# Assignment-1.net
KiCad netlist of a schematic drawn in EAGLE
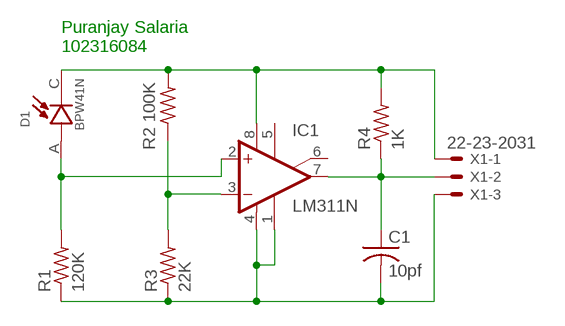
[diagram p0: schematic, sheet 1]

(export (version "E")
  (design (tool "Eeschema 10.0.6"))
  (components
    (comp (ref "C1")
      (value "10pf")
      (footprint "eagle-import:C025-050X050")
      (libsource (lib "eagle-import") (part "C-US025-050X050"))
    )
    (comp (ref "D1")
      (value "BPW41N")
      (footprint "eagle-import:DIO_BPW41N")
      (fields (field (name "MF") "Vishay Semiconductor Opto Division"))
      (libsource (lib "eagle-import") (part "BPW41N"))
    )
    (comp (ref "IC1")
      (value "LM311N")
      (footprint "eagle-import:DIL08")
      (libsource (lib "eagle-import") (part "LM311N"))
    )
    (comp (ref "R1")
      (value "120K")
      (footprint "eagle-import:0204_7")
      (libsource (lib "eagle-import") (part "R-US_0204/7"))
    )
    (comp (ref "R2")
      (value "R2 100K")
      (footprint "eagle-import:0204_7")
      (libsource (lib "eagle-import") (part "R-US_0204/7"))
    )
    (comp (ref "R3")
      (value "22K")
      (footprint "eagle-import:0204_7")
      (libsource (lib "eagle-import") (part "R-US_0204/7"))
    )
    (comp (ref "R4")
      (value "1K")
      (footprint "eagle-import:0204_7")
      (libsource (lib "eagle-import") (part "R-US_0204/7"))
    )
    (comp (ref "X1")
      (value "22-23-2031")
      (footprint "eagle-import:22-23-2031")
      (fields (field (name "MF") "MOLEX"))
      (libsource (lib "eagle-import") (part "22-23-2031"))
    )
  )
  (nets
    (net (code "1") (name "Net-(IC1-+IN)") (class "Default")
      (node (ref "D1") (pin "A") (pinfunction "A_A") (pintype "passive"))
      (node (ref "IC1") (pin "2") (pinfunction "+IN_2") (pintype "input"))
      (node (ref "R1") (pin "2") (pinfunction "2_2") (pintype "passive"))
    )
    (net (code "2") (name "Net-(IC1--IN)") (class "Default")
      (node (ref "IC1") (pin "3") (pinfunction "-IN_3") (pintype "input"))
      (node (ref "R2") (pin "1") (pinfunction "1_1") (pintype "passive"))
      (node (ref "R3") (pin "2") (pinfunction "2_2") (pintype "passive"))
    )
    (net (code "3") (name "Net-(IC1-GND)") (class "Default")
      (node (ref "C1") (pin "2") (pinfunction "2_2") (pintype "passive"))
      (node (ref "IC1") (pin "1") (pinfunction "GND_1") (pintype "passive"))
      (node (ref "IC1") (pin "4") (pinfunction "V-_4") (pintype "power_in"))
      (node (ref "R1") (pin "1") (pinfunction "1_1") (pintype "passive"))
      (node (ref "R3") (pin "1") (pinfunction "1_1") (pintype "passive"))
      (node (ref "X1") (pin "3") (pinfunction "S_3") (pintype "passive"))
    )
    (net (code "4") (name "Net-(IC1-OUT)") (class "Default")
      (node (ref "C1") (pin "1") (pinfunction "1_1") (pintype "passive"))
      (node (ref "IC1") (pin "7") (pinfunction "OUT_7") (pintype "output"))
      (node (ref "R4") (pin "1") (pinfunction "1_1") (pintype "passive"))
      (node (ref "X1") (pin "2") (pinfunction "S_2") (pintype "passive"))
    )
    (net (code "5") (name "Net-(IC1-V+)") (class "Default")
      (node (ref "D1") (pin "C") (pinfunction "C_C") (pintype "passive"))
      (node (ref "IC1") (pin "8") (pinfunction "V+_8") (pintype "power_in"))
      (node (ref "R2") (pin "2") (pinfunction "2_2") (pintype "passive"))
      (node (ref "R4") (pin "2") (pinfunction "2_2") (pintype "passive"))
      (node (ref "X1") (pin "1") (pinfunction "S_1") (pintype "passive"))
    )
    (net (code "6") (name "unconnected-(IC1-ON-Pad5)") (class "Default")
      (node (ref "IC1") (pin "5") (pinfunction "ON_5") (pintype "passive"))
    )
    (net (code "7") (name "unconnected-(IC1-ON{slash}STR-Pad6)") (class "Default")
      (node (ref "IC1") (pin "6") (pinfunction "ON/STR_6") (pintype "passive"))
    )
  )
)
